# ASD2614.net
KiCad netlist of a schematic drawn in EAGLE
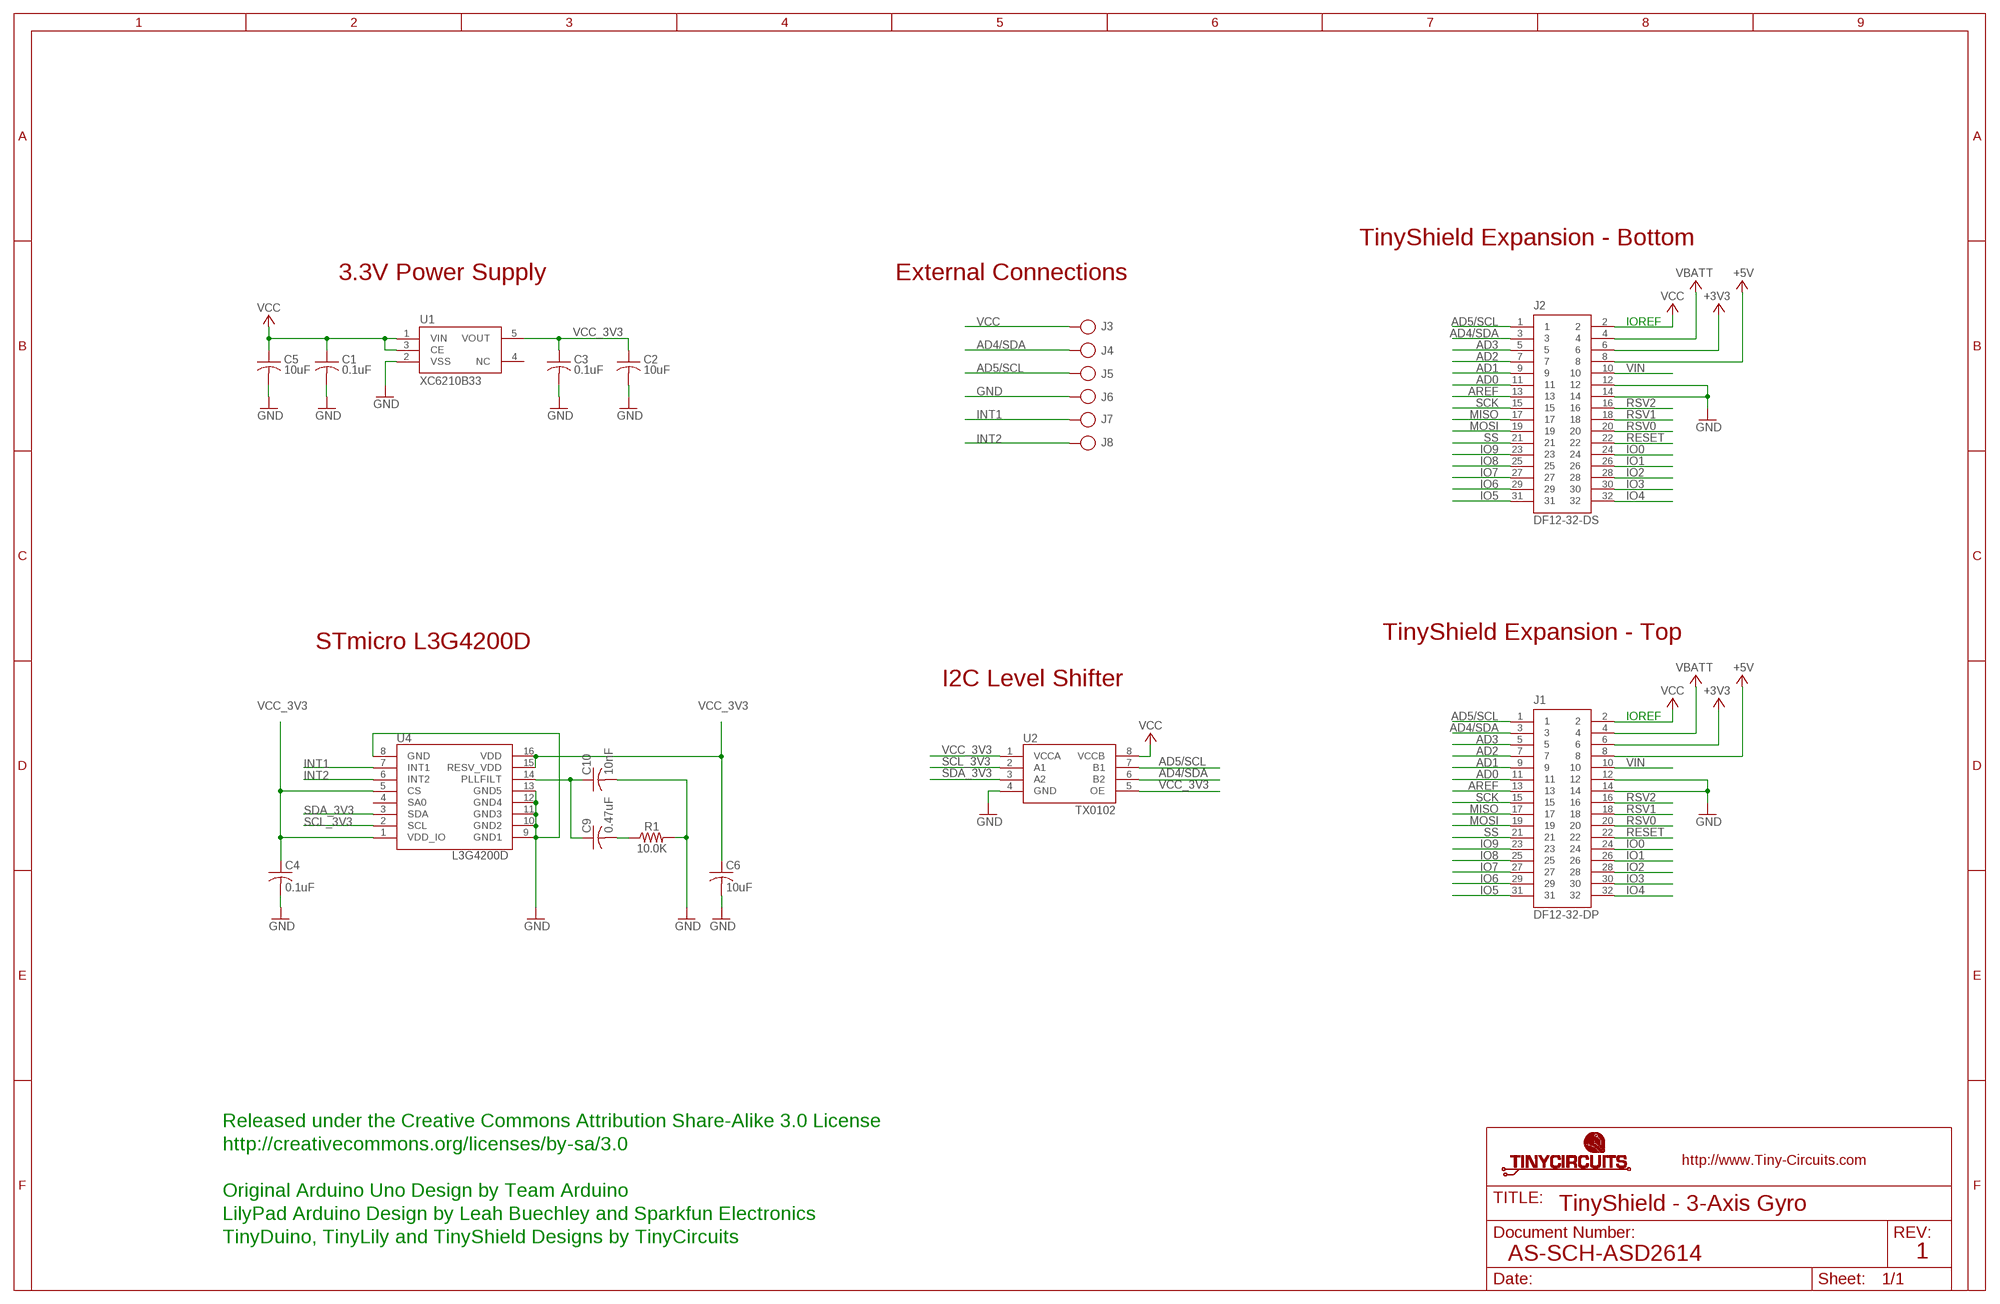
[diagram p0: schematic, sheet 1]

(export (version "E")
  (design (tool "Eeschema 10.0.6"))
  (components
    (comp (ref "C1")
      (value "0.1uF")
      (footprint "eagle-import:C0402")
      (fields (field (name "PARTNO") "AS-ITM-00008") (field (name "PARTNO_1") "AS-ITM-00008"))
      (libsource (lib "eagle-import") (part "AS-ITM-00008"))
    )
    (comp (ref "C2")
      (value "10uF")
      (footprint "eagle-import:C0805")
      (fields (field (name "PARTNO") "AS-ITM-00045") (field (name "PARTNO_1") "AS-ITM-00045"))
      (libsource (lib "eagle-import") (part "AS-ITM-00045"))
    )
    (comp (ref "C3")
      (value "0.1uF")
      (footprint "eagle-import:C0402")
      (fields (field (name "PARTNO") "AS-ITM-00008") (field (name "PARTNO_1") "AS-ITM-00008"))
      (libsource (lib "eagle-import") (part "AS-ITM-00008"))
    )
    (comp (ref "C4")
      (value "0.1uF")
      (footprint "eagle-import:C0402")
      (fields (field (name "PARTNO") "AS-ITM-00008"))
      (libsource (lib "eagle-import") (part "AS-ITM-00008"))
    )
    (comp (ref "C5")
      (value "10uF")
      (footprint "eagle-import:C0805")
      (fields (field (name "PARTNO") "AS-ITM-00045"))
      (libsource (lib "eagle-import") (part "AS-ITM-00045"))
    )
    (comp (ref "C6")
      (value "10uF")
      (footprint "eagle-import:C0603")
      (fields (field (name "PARTNO") "AS-ITM-00002"))
      (libsource (lib "eagle-import") (part "AS-ITM-00002"))
    )
    (comp (ref "C9")
      (value "0.47uF")
      (footprint "eagle-import:C0402")
      (libsource (lib "eagle-import") (part "AS-ITM-00090"))
    )
    (comp (ref "C10")
      (value "10nF")
      (footprint "eagle-import:0402")
      (fields (field (name "PARTNO") "AS-ITM-00084"))
      (libsource (lib "eagle-import") (part "AS-ITM-00084"))
    )
    (comp (ref "J1")
      (value "DF12-32-DP")
      (footprint "eagle-import:DF12-32-DP")
      (fields (field (name "PARTNO") "AS-ITM-00015") (field (name "PARTNO_1") "AS-ITM-00015"))
      (libsource (lib "eagle-import") (part "AS-ITM-00015"))
    )
    (comp (ref "J2")
      (value "DF12-32-DS")
      (footprint "eagle-import:DF12-32-DS")
      (fields (field (name "PARTNO") "AS-ITM-00012") (field (name "PARTNO_1") "AS-ITM-00012"))
      (libsource (lib "eagle-import") (part "AS-ITM-00012"))
    )
    (comp (ref "J3")
      (value "PIN_1X.1\"")
      (footprint "eagle-import:1X.1_")
      (libsource (lib "eagle-import") (part "PIN_1X.1{dblquote}"))
    )
    (comp (ref "J4")
      (value "PIN_1X.1\"")
      (footprint "eagle-import:1X.1_")
      (libsource (lib "eagle-import") (part "PIN_1X.1{dblquote}"))
    )
    (comp (ref "J5")
      (value "PIN_1X.1\"")
      (footprint "eagle-import:1X.1_")
      (libsource (lib "eagle-import") (part "PIN_1X.1{dblquote}"))
    )
    (comp (ref "J6")
      (value "PIN_1X.1\"")
      (footprint "eagle-import:1X.1_")
      (libsource (lib "eagle-import") (part "PIN_1X.1{dblquote}"))
    )
    (comp (ref "J7")
      (value "PIN_1X.1\"")
      (footprint "eagle-import:1X.1_")
      (libsource (lib "eagle-import") (part "PIN_1X.1{dblquote}"))
    )
    (comp (ref "J8")
      (value "PIN_1X.1\"")
      (footprint "eagle-import:1X.1_")
      (libsource (lib "eagle-import") (part "PIN_1X.1{dblquote}"))
    )
    (comp (ref "R1")
      (value "10.0K")
      (footprint "eagle-import:0402")
      (fields (field (name "PARTNO") "AS-ITM-00032"))
      (libsource (lib "eagle-import") (part "AS-ITM-00032"))
    )
    (comp (ref "U1")
      (value "XC6210B33")
      (footprint "eagle-import:SOT-25")
      (fields (field (name "PARTNO") "AS-ITM-00046"))
      (libsource (lib "eagle-import") (part "AS-ITM-00046"))
    )
    (comp (ref "U2")
      (value "TX0102")
      (footprint "eagle-import:DQE(R-PX2SON-N8)")
      (fields (field (name "PARTNO") "AS-ITM-00073"))
      (libsource (lib "eagle-import") (part "AS-ITM-00073"))
    )
    (comp (ref "U4")
      (value "L3G4200D")
      (footprint "eagle-import:L3G4200D")
      (fields (field (name "PARTNO") "AS-ITM-00089"))
      (libsource (lib "eagle-import") (part "AS-ITM-00089"))
    )
  )
  (nets
    (net (code "1") (name "+3V3") (class "Default")
      (node (ref "J1") (pin "6") (pinfunction "6_6") (pintype "bidirectional"))
      (node (ref "J2") (pin "6") (pinfunction "6_6") (pintype "bidirectional"))
    )
    (net (code "2") (name "+5V") (class "Default")
      (node (ref "J1") (pin "8") (pinfunction "8_8") (pintype "bidirectional"))
      (node (ref "J2") (pin "8") (pinfunction "8_8") (pintype "bidirectional"))
    )
    (net (code "3") (name "/AD0") (class "Default")
      (node (ref "J1") (pin "11") (pinfunction "11_11") (pintype "bidirectional"))
      (node (ref "J2") (pin "11") (pinfunction "11_11") (pintype "bidirectional"))
    )
    (net (code "4") (name "/AD1") (class "Default")
      (node (ref "J1") (pin "9") (pinfunction "9_9") (pintype "bidirectional"))
      (node (ref "J2") (pin "9") (pinfunction "9_9") (pintype "bidirectional"))
    )
    (net (code "5") (name "/AD2") (class "Default")
      (node (ref "J1") (pin "7") (pinfunction "7_7") (pintype "bidirectional"))
      (node (ref "J2") (pin "7") (pinfunction "7_7") (pintype "bidirectional"))
    )
    (net (code "6") (name "/AD3") (class "Default")
      (node (ref "J1") (pin "5") (pinfunction "5_5") (pintype "bidirectional"))
      (node (ref "J2") (pin "5") (pinfunction "5_5") (pintype "bidirectional"))
    )
    (net (code "7") (name "/AD4{slash}SDA") (class "Default")
      (node (ref "J1") (pin "3") (pinfunction "3_3") (pintype "bidirectional"))
      (node (ref "J2") (pin "3") (pinfunction "3_3") (pintype "bidirectional"))
      (node (ref "J4") (pin "1") (pinfunction "1_1") (pintype "bidirectional"))
      (node (ref "U2") (pin "6") (pinfunction "B2_6") (pintype "bidirectional"))
    )
    (net (code "8") (name "/AD5{slash}SCL") (class "Default")
      (node (ref "J1") (pin "1") (pinfunction "1_1") (pintype "bidirectional"))
      (node (ref "J2") (pin "1") (pinfunction "1_1") (pintype "bidirectional"))
      (node (ref "J5") (pin "1") (pinfunction "1_1") (pintype "bidirectional"))
      (node (ref "U2") (pin "7") (pinfunction "B1_7") (pintype "bidirectional"))
    )
    (net (code "9") (name "/AREF") (class "Default")
      (node (ref "J1") (pin "13") (pinfunction "13_13") (pintype "bidirectional"))
      (node (ref "J2") (pin "13") (pinfunction "13_13") (pintype "bidirectional"))
    )
    (net (code "10") (name "/INT1") (class "Default")
      (node (ref "J7") (pin "1") (pinfunction "1_1") (pintype "bidirectional"))
      (node (ref "U4") (pin "7") (pinfunction "INT1_7") (pintype "bidirectional"))
    )
    (net (code "11") (name "/INT2") (class "Default")
      (node (ref "J8") (pin "1") (pinfunction "1_1") (pintype "bidirectional"))
      (node (ref "U4") (pin "6") (pinfunction "INT2_6") (pintype "bidirectional"))
    )
    (net (code "12") (name "/IO0") (class "Default")
      (node (ref "J1") (pin "24") (pinfunction "24_24") (pintype "bidirectional"))
      (node (ref "J2") (pin "24") (pinfunction "24_24") (pintype "bidirectional"))
    )
    (net (code "13") (name "/IO1") (class "Default")
      (node (ref "J1") (pin "26") (pinfunction "26_26") (pintype "bidirectional"))
      (node (ref "J2") (pin "26") (pinfunction "26_26") (pintype "bidirectional"))
    )
    (net (code "14") (name "/IO2") (class "Default")
      (node (ref "J1") (pin "28") (pinfunction "28_28") (pintype "bidirectional"))
      (node (ref "J2") (pin "28") (pinfunction "28_28") (pintype "bidirectional"))
    )
    (net (code "15") (name "/IO3") (class "Default")
      (node (ref "J1") (pin "30") (pinfunction "30_30") (pintype "bidirectional"))
      (node (ref "J2") (pin "30") (pinfunction "30_30") (pintype "bidirectional"))
    )
    (net (code "16") (name "/IO4") (class "Default")
      (node (ref "J1") (pin "32") (pinfunction "32_32") (pintype "bidirectional"))
      (node (ref "J2") (pin "32") (pinfunction "32_32") (pintype "bidirectional"))
    )
    (net (code "17") (name "/IO5") (class "Default")
      (node (ref "J1") (pin "31") (pinfunction "31_31") (pintype "bidirectional"))
      (node (ref "J2") (pin "31") (pinfunction "31_31") (pintype "bidirectional"))
    )
    (net (code "18") (name "/IO6") (class "Default")
      (node (ref "J1") (pin "29") (pinfunction "29_29") (pintype "bidirectional"))
      (node (ref "J2") (pin "29") (pinfunction "29_29") (pintype "bidirectional"))
    )
    (net (code "19") (name "/IO7") (class "Default")
      (node (ref "J1") (pin "27") (pinfunction "27_27") (pintype "bidirectional"))
      (node (ref "J2") (pin "27") (pinfunction "27_27") (pintype "bidirectional"))
    )
    (net (code "20") (name "/IO8") (class "Default")
      (node (ref "J1") (pin "25") (pinfunction "25_25") (pintype "bidirectional"))
      (node (ref "J2") (pin "25") (pinfunction "25_25") (pintype "bidirectional"))
    )
    (net (code "21") (name "/IO9") (class "Default")
      (node (ref "J1") (pin "23") (pinfunction "23_23") (pintype "bidirectional"))
      (node (ref "J2") (pin "23") (pinfunction "23_23") (pintype "bidirectional"))
    )
    (net (code "22") (name "/MISO") (class "Default")
      (node (ref "J1") (pin "17") (pinfunction "17_17") (pintype "bidirectional"))
      (node (ref "J2") (pin "17") (pinfunction "17_17") (pintype "bidirectional"))
    )
    (net (code "23") (name "/MOSI") (class "Default")
      (node (ref "J1") (pin "19") (pinfunction "19_19") (pintype "bidirectional"))
      (node (ref "J2") (pin "19") (pinfunction "19_19") (pintype "bidirectional"))
    )
    (net (code "24") (name "/RESET") (class "Default")
      (node (ref "J1") (pin "22") (pinfunction "22_22") (pintype "bidirectional"))
      (node (ref "J2") (pin "22") (pinfunction "22_22") (pintype "bidirectional"))
    )
    (net (code "25") (name "/RSV0") (class "Default")
      (node (ref "J1") (pin "20") (pinfunction "20_20") (pintype "bidirectional"))
      (node (ref "J2") (pin "20") (pinfunction "20_20") (pintype "bidirectional"))
    )
    (net (code "26") (name "/RSV1") (class "Default")
      (node (ref "J1") (pin "18") (pinfunction "18_18") (pintype "bidirectional"))
      (node (ref "J2") (pin "18") (pinfunction "18_18") (pintype "bidirectional"))
    )
    (net (code "27") (name "/RSV2") (class "Default")
      (node (ref "J1") (pin "16") (pinfunction "16_16") (pintype "bidirectional"))
      (node (ref "J2") (pin "16") (pinfunction "16_16") (pintype "bidirectional"))
    )
    (net (code "28") (name "/SCK") (class "Default")
      (node (ref "J1") (pin "15") (pinfunction "15_15") (pintype "bidirectional"))
      (node (ref "J2") (pin "15") (pinfunction "15_15") (pintype "bidirectional"))
    )
    (net (code "29") (name "/SCL_3V3") (class "Default")
      (node (ref "U2") (pin "2") (pinfunction "A1_2") (pintype "bidirectional"))
      (node (ref "U4") (pin "2") (pinfunction "SCL_2") (pintype "bidirectional"))
    )
    (net (code "30") (name "/SDA_3V3") (class "Default")
      (node (ref "U2") (pin "3") (pinfunction "A2_3") (pintype "bidirectional"))
      (node (ref "U4") (pin "3") (pinfunction "SDA_3") (pintype "bidirectional"))
    )
    (net (code "31") (name "/SS") (class "Default")
      (node (ref "J1") (pin "21") (pinfunction "21_21") (pintype "bidirectional"))
      (node (ref "J2") (pin "21") (pinfunction "21_21") (pintype "bidirectional"))
    )
    (net (code "32") (name "/VCC_3V3") (class "Default")
      (node (ref "C2") (pin "1") (pinfunction "1_1") (pintype "passive"))
      (node (ref "C3") (pin "1") (pinfunction "1_1") (pintype "passive"))
      (node (ref "C4") (pin "1") (pinfunction "1_1") (pintype "passive"))
      (node (ref "C6") (pin "1") (pinfunction "1_1") (pintype "passive"))
      (node (ref "U1") (pin "5") (pinfunction "VOUT_5") (pintype "bidirectional"))
      (node (ref "U2") (pin "1") (pinfunction "VCCA_1") (pintype "bidirectional"))
      (node (ref "U2") (pin "5") (pinfunction "OE_5") (pintype "bidirectional"))
      (node (ref "U4") (pin "1") (pinfunction "VDD_IO_1") (pintype "bidirectional"))
      (node (ref "U4") (pin "15") (pinfunction "RESV_VDD_15") (pintype "bidirectional"))
      (node (ref "U4") (pin "16") (pinfunction "VDD_16") (pintype "bidirectional"))
      (node (ref "U4") (pin "5") (pinfunction "CS_5") (pintype "bidirectional"))
    )
    (net (code "33") (name "/VIN") (class "Default")
      (node (ref "J1") (pin "10") (pinfunction "10_10") (pintype "bidirectional"))
      (node (ref "J2") (pin "10") (pinfunction "10_10") (pintype "bidirectional"))
    )
    (net (code "34") (name "GND") (class "Default")
      (node (ref "C1") (pin "2") (pinfunction "2_2") (pintype "passive"))
      (node (ref "C10") (pin "2") (pinfunction "2_2") (pintype "passive"))
      (node (ref "C2") (pin "2") (pinfunction "2_2") (pintype "passive"))
      (node (ref "C3") (pin "2") (pinfunction "2_2") (pintype "passive"))
      (node (ref "C4") (pin "2") (pinfunction "2_2") (pintype "passive"))
      (node (ref "C5") (pin "2") (pinfunction "2_2") (pintype "passive"))
      (node (ref "C6") (pin "2") (pinfunction "2_2") (pintype "passive"))
      (node (ref "J1") (pin "12") (pinfunction "12_12") (pintype "bidirectional"))
      (node (ref "J1") (pin "14") (pinfunction "14_14") (pintype "bidirectional"))
      (node (ref "J2") (pin "12") (pinfunction "12_12") (pintype "bidirectional"))
      (node (ref "J2") (pin "14") (pinfunction "14_14") (pintype "bidirectional"))
      (node (ref "J6") (pin "1") (pinfunction "1_1") (pintype "bidirectional"))
      (node (ref "R1") (pin "2") (pinfunction "2_2") (pintype "passive"))
      (node (ref "U1") (pin "2") (pinfunction "VSS_2") (pintype "power_in"))
      (node (ref "U2") (pin "4") (pinfunction "GND_4") (pintype "bidirectional"))
      (node (ref "U4") (pin "10") (pinfunction "GND2_10") (pintype "bidirectional"))
      (node (ref "U4") (pin "11") (pinfunction "GND3_11") (pintype "bidirectional"))
      (node (ref "U4") (pin "12") (pinfunction "GND4_12") (pintype "bidirectional"))
      (node (ref "U4") (pin "13") (pinfunction "GND5_13") (pintype "bidirectional"))
      (node (ref "U4") (pin "8") (pinfunction "GND_8") (pintype "bidirectional"))
      (node (ref "U4") (pin "9") (pinfunction "GND1_9") (pintype "bidirectional"))
    )
    (net (code "35") (name "Net-(C9-Pad2)") (class "Default")
      (node (ref "C9") (pin "2") (pinfunction "2_2") (pintype "passive"))
      (node (ref "R1") (pin "1") (pinfunction "1_1") (pintype "passive"))
    )
    (net (code "36") (name "Net-(U4-PLLFILT)") (class "Default")
      (node (ref "C10") (pin "1") (pinfunction "1_1") (pintype "passive"))
      (node (ref "C9") (pin "1") (pinfunction "1_1") (pintype "passive"))
      (node (ref "U4") (pin "14") (pinfunction "PLLFILT_14") (pintype "bidirectional"))
    )
    (net (code "37") (name "VBATT") (class "Default")
      (node (ref "J1") (pin "4") (pinfunction "4_4") (pintype "bidirectional"))
      (node (ref "J2") (pin "4") (pinfunction "4_4") (pintype "bidirectional"))
    )
    (net (code "38") (name "VCC") (class "Default")
      (node (ref "C1") (pin "1") (pinfunction "1_1") (pintype "passive"))
      (node (ref "C5") (pin "1") (pinfunction "1_1") (pintype "passive"))
      (node (ref "J1") (pin "2") (pinfunction "2_2") (pintype "bidirectional"))
      (node (ref "J2") (pin "2") (pinfunction "2_2") (pintype "bidirectional"))
      (node (ref "J3") (pin "1") (pinfunction "1_1") (pintype "bidirectional"))
      (node (ref "U1") (pin "1") (pinfunction "VIN_1") (pintype "bidirectional"))
      (node (ref "U1") (pin "3") (pinfunction "CE_3") (pintype "bidirectional"))
      (node (ref "U2") (pin "8") (pinfunction "VCCB_8") (pintype "bidirectional"))
    )
    (net (code "39") (name "unconnected-(U1-NC-Pad4)") (class "Default")
      (node (ref "U1") (pin "4") (pinfunction "NC_4") (pintype "bidirectional"))
    )
    (net (code "40") (name "unconnected-(U4-SA0-Pad4)") (class "Default")
      (node (ref "U4") (pin "4") (pinfunction "SA0_4") (pintype "bidirectional"))
    )
  )
)
